# Rapide555.net
KiCad netlist of a schematic drawn in EAGLE
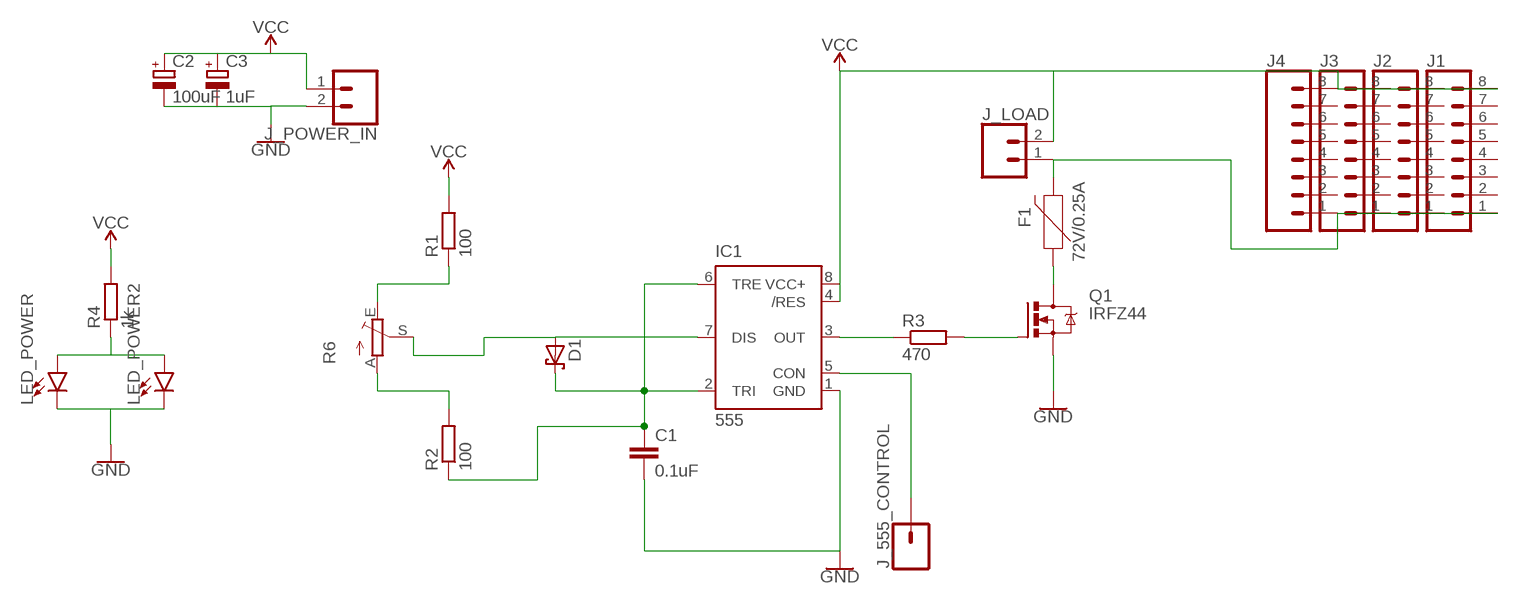
[diagram p0: schematic, sheet 1]

(export (version "E")
  (design (tool "Eeschema 10.0.6"))
  (components
    (comp (ref "C1")
      (value "0.1uF")
      (footprint "eagle-import:C025-025X050")
      (libsource (lib "eagle-import") (part "C-EU025-025X050"))
    )
    (comp (ref "C2")
      (value "100uF")
      (footprint "eagle-import:E5-5")
      (libsource (lib "eagle-import") (part "CPOL-EUE5-5"))
    )
    (comp (ref "C3")
      (value "1uF")
      (footprint "eagle-import:E2,5-6E")
      (libsource (lib "eagle-import") (part "CPOL-EUE2,5-6E"))
    )
    (comp (ref "D1")
      (value "SCHOTTKY-DIODEDO35-7")
      (footprint "eagle-import:DO35-7")
      (libsource (lib "eagle-import") (part "SCHOTTKY-DIODEDO35-7"))
    )
    (comp (ref "F1")
      (value "72V/0.25A")
      (footprint "eagle-import:PTH")
      (libsource (lib "eagle-import") (part "PPTC_PTH"))
    )
    (comp (ref "IC1")
      (value "555")
      (footprint "eagle-import:DIP08")
      (libsource (lib "eagle-import") (part "555P"))
    )
    (comp (ref "J1")
      (value "CONN_08NO_SILK_FEMALE_PTH")
      (footprint "eagle-import:1X08_NO_SILK")
      (libsource (lib "eagle-import") (part "CONN_08NO_SILK_FEMALE_PTH"))
    )
    (comp (ref "J2")
      (value "CONN_08NO_SILK_FEMALE_PTH")
      (footprint "eagle-import:1X08_NO_SILK")
      (libsource (lib "eagle-import") (part "CONN_08NO_SILK_FEMALE_PTH"))
    )
    (comp (ref "J3")
      (value "CONN_08NO_SILK_FEMALE_PTH")
      (footprint "eagle-import:1X08_NO_SILK")
      (libsource (lib "eagle-import") (part "CONN_08NO_SILK_FEMALE_PTH"))
    )
    (comp (ref "J4")
      (value "CONN_08NO_SILK_FEMALE_PTH")
      (footprint "eagle-import:1X08_NO_SILK")
      (libsource (lib "eagle-import") (part "CONN_08NO_SILK_FEMALE_PTH"))
    )
    (comp (ref "J_555_CONTROL")
      (value "CONN_01")
      (footprint "eagle-import:1X01")
      (libsource (lib "eagle-import") (part "CONN_01"))
    )
    (comp (ref "J_LOAD")
      (value "CONN_023.5MM")
      (footprint "eagle-import:SCREWTERMINAL-3.5MM-2")
      (libsource (lib "eagle-import") (part "CONN_023.5MM"))
    )
    (comp (ref "J_POWER_IN")
      (value "CONN_023.5MM")
      (footprint "eagle-import:SCREWTERMINAL-3.5MM-2")
      (libsource (lib "eagle-import") (part "CONN_023.5MM"))
    )
    (comp (ref "LED_POWER")
      (value "LED3MM")
      (footprint "eagle-import:LED_3MM")
      (libsource (lib "eagle-import") (part "LED3MM"))
    )
    (comp (ref "LED_POWER2")
      (value "LED-FKIT-1206")
      (footprint "eagle-import:FKIT-LED-1206")
      (libsource (lib "eagle-import") (part "LED-FKIT-1206"))
    )
    (comp (ref "Q1")
      (value "IRFZ44")
      (footprint "eagle-import:TO-247AD-V")
      (libsource (lib "eagle-import") (part "IXF?6NH90"))
    )
    (comp (ref "R1")
      (value "100")
      (footprint "eagle-import:0204_5")
      (libsource (lib "eagle-import") (part "R-EU_0204/5"))
    )
    (comp (ref "R2")
      (value "100")
      (footprint "eagle-import:0204V")
      (libsource (lib "eagle-import") (part "R-EU_0204/2V"))
    )
    (comp (ref "R3")
      (value "470")
      (footprint "eagle-import:0204_5")
      (libsource (lib "eagle-import") (part "R-EU_0204/5"))
    )
    (comp (ref "R4")
      (value "1k")
      (footprint "eagle-import:0204V")
      (libsource (lib "eagle-import") (part "R-EU_0204/2V"))
    )
    (comp (ref "R6")
      (value "TRIM_EU-B25P")
      (footprint "eagle-import:B25P")
      (libsource (lib "eagle-import") (part "TRIM_EU-B25P"))
    )
  )
  (nets
    (net (code "1") (name "GND") (class "Default")
      (node (ref "C1") (pin "2") (pinfunction "2_2") (pintype "passive"))
      (node (ref "C2") (pin "-") (pinfunction "-_-") (pintype "passive"))
      (node (ref "C3") (pin "-") (pinfunction "-_-") (pintype "passive"))
      (node (ref "IC1") (pin "1") (pinfunction "GND_1") (pintype "power_in"))
      (node (ref "J_POWER_IN") (pin "2") (pinfunction "2_2") (pintype "passive"))
      (node (ref "LED_POWER") (pin "K") (pinfunction "C_K") (pintype "passive"))
      (node (ref "LED_POWER2") (pin "C") (pinfunction "C_C") (pintype "passive"))
      (node (ref "Q1") (pin "S") (pinfunction "S_S") (pintype "passive"))
    )
    (net (code "2") (name "Net-(F1-1)") (class "Default")
      (node (ref "F1") (pin "P$1") (pinfunction "1_P$1") (pintype "bidirectional"))
      (node (ref "Q1") (pin "D") (pinfunction "D_D") (pintype "passive"))
    )
    (net (code "3") (name "Net-(F1-2)") (class "Default")
      (node (ref "F1") (pin "P$2") (pinfunction "2_P$2") (pintype "bidirectional"))
      (node (ref "J1") (pin "1") (pinfunction "1_1") (pintype "passive"))
      (node (ref "J2") (pin "1") (pinfunction "1_1") (pintype "passive"))
      (node (ref "J3") (pin "1") (pinfunction "1_1") (pintype "passive"))
      (node (ref "J4") (pin "1") (pinfunction "1_1") (pintype "passive"))
      (node (ref "J_LOAD") (pin "1") (pinfunction "1_1") (pintype "passive"))
    )
    (net (code "4") (name "Net-(IC1-CON)") (class "Default")
      (node (ref "IC1") (pin "5") (pinfunction "CON_5") (pintype "input"))
      (node (ref "J_555_CONTROL") (pin "1") (pinfunction "1_1") (pintype "passive"))
    )
    (net (code "5") (name "Net-(IC1-DIS)") (class "Default")
      (node (ref "D1") (pin "A") (pinfunction "A_A") (pintype "passive"))
      (node (ref "IC1") (pin "7") (pinfunction "DIS_7") (pintype "input"))
      (node (ref "R6") (pin "S") (pinfunction "S_S") (pintype "passive"))
    )
    (net (code "6") (name "Net-(IC1-OUT)") (class "Default")
      (node (ref "IC1") (pin "3") (pinfunction "OUT_3") (pintype "output"))
      (node (ref "R3") (pin "1") (pinfunction "1_1") (pintype "passive"))
    )
    (net (code "7") (name "Net-(IC1-TRE)") (class "Default")
      (node (ref "C1") (pin "1") (pinfunction "1_1") (pintype "passive"))
      (node (ref "D1") (pin "C") (pinfunction "C_C") (pintype "passive"))
      (node (ref "IC1") (pin "2") (pinfunction "TRI_2") (pintype "input"))
      (node (ref "IC1") (pin "6") (pinfunction "TRE_6") (pintype "input"))
      (node (ref "R2") (pin "1") (pinfunction "1_1") (pintype "passive"))
    )
    (net (code "8") (name "Net-(LED_POWER-PadA)") (class "Default")
      (node (ref "LED_POWER") (pin "A") (pinfunction "A_A") (pintype "passive"))
      (node (ref "LED_POWER2") (pin "A") (pinfunction "A_A") (pintype "passive"))
      (node (ref "R4") (pin "1") (pinfunction "1_1") (pintype "passive"))
    )
    (net (code "9") (name "Net-(Q1-PadG)") (class "Default")
      (node (ref "Q1") (pin "G") (pinfunction "G_G") (pintype "passive"))
      (node (ref "R3") (pin "2") (pinfunction "2_2") (pintype "passive"))
    )
    (net (code "10") (name "Net-(R1-Pad1)") (class "Default")
      (node (ref "R1") (pin "1") (pinfunction "1_1") (pintype "passive"))
      (node (ref "R6") (pin "E") (pinfunction "E_E") (pintype "passive"))
    )
    (net (code "11") (name "Net-(R2-Pad2)") (class "Default")
      (node (ref "R2") (pin "2") (pinfunction "2_2") (pintype "passive"))
      (node (ref "R6") (pin "A") (pinfunction "A_A") (pintype "passive"))
    )
    (net (code "12") (name "VCC") (class "Default")
      (node (ref "C2") (pin "+") (pinfunction "+_+") (pintype "passive"))
      (node (ref "C3") (pin "+") (pinfunction "+_+") (pintype "passive"))
      (node (ref "IC1") (pin "4") (pinfunction "/RES_4") (pintype "input"))
      (node (ref "IC1") (pin "8") (pinfunction "VCC+_8") (pintype "power_in"))
      (node (ref "J1") (pin "8") (pinfunction "8_8") (pintype "passive"))
      (node (ref "J2") (pin "8") (pinfunction "8_8") (pintype "passive"))
      (node (ref "J3") (pin "8") (pinfunction "8_8") (pintype "passive"))
      (node (ref "J4") (pin "8") (pinfunction "8_8") (pintype "passive"))
      (node (ref "J_LOAD") (pin "2") (pinfunction "2_2") (pintype "passive"))
      (node (ref "J_POWER_IN") (pin "1") (pinfunction "1_1") (pintype "passive"))
      (node (ref "R1") (pin "2") (pinfunction "2_2") (pintype "passive"))
      (node (ref "R4") (pin "2") (pinfunction "2_2") (pintype "passive"))
    )
    (net (code "13") (name "unconnected-(J1-Pad2)") (class "Default")
      (node (ref "J1") (pin "2") (pinfunction "2_2") (pintype "passive"))
    )
    (net (code "14") (name "unconnected-(J1-Pad3)") (class "Default")
      (node (ref "J1") (pin "3") (pinfunction "3_3") (pintype "passive"))
    )
    (net (code "15") (name "unconnected-(J1-Pad4)") (class "Default")
      (node (ref "J1") (pin "4") (pinfunction "4_4") (pintype "passive"))
    )
    (net (code "16") (name "unconnected-(J1-Pad5)") (class "Default")
      (node (ref "J1") (pin "5") (pinfunction "5_5") (pintype "passive"))
    )
    (net (code "17") (name "unconnected-(J1-Pad6)") (class "Default")
      (node (ref "J1") (pin "6") (pinfunction "6_6") (pintype "passive"))
    )
    (net (code "18") (name "unconnected-(J1-Pad7)") (class "Default")
      (node (ref "J1") (pin "7") (pinfunction "7_7") (pintype "passive"))
    )
    (net (code "19") (name "unconnected-(J2-Pad2)") (class "Default")
      (node (ref "J2") (pin "2") (pinfunction "2_2") (pintype "passive"))
    )
    (net (code "20") (name "unconnected-(J2-Pad3)") (class "Default")
      (node (ref "J2") (pin "3") (pinfunction "3_3") (pintype "passive"))
    )
    (net (code "21") (name "unconnected-(J2-Pad4)") (class "Default")
      (node (ref "J2") (pin "4") (pinfunction "4_4") (pintype "passive"))
    )
    (net (code "22") (name "unconnected-(J2-Pad5)") (class "Default")
      (node (ref "J2") (pin "5") (pinfunction "5_5") (pintype "passive"))
    )
    (net (code "23") (name "unconnected-(J2-Pad6)") (class "Default")
      (node (ref "J2") (pin "6") (pinfunction "6_6") (pintype "passive"))
    )
    (net (code "24") (name "unconnected-(J2-Pad7)") (class "Default")
      (node (ref "J2") (pin "7") (pinfunction "7_7") (pintype "passive"))
    )
    (net (code "25") (name "unconnected-(J3-Pad2)") (class "Default")
      (node (ref "J3") (pin "2") (pinfunction "2_2") (pintype "passive"))
    )
    (net (code "26") (name "unconnected-(J3-Pad3)") (class "Default")
      (node (ref "J3") (pin "3") (pinfunction "3_3") (pintype "passive"))
    )
    (net (code "27") (name "unconnected-(J3-Pad4)") (class "Default")
      (node (ref "J3") (pin "4") (pinfunction "4_4") (pintype "passive"))
    )
    (net (code "28") (name "unconnected-(J3-Pad5)") (class "Default")
      (node (ref "J3") (pin "5") (pinfunction "5_5") (pintype "passive"))
    )
    (net (code "29") (name "unconnected-(J3-Pad6)") (class "Default")
      (node (ref "J3") (pin "6") (pinfunction "6_6") (pintype "passive"))
    )
    (net (code "30") (name "unconnected-(J3-Pad7)") (class "Default")
      (node (ref "J3") (pin "7") (pinfunction "7_7") (pintype "passive"))
    )
    (net (code "31") (name "unconnected-(J4-Pad2)") (class "Default")
      (node (ref "J4") (pin "2") (pinfunction "2_2") (pintype "passive"))
    )
    (net (code "32") (name "unconnected-(J4-Pad3)") (class "Default")
      (node (ref "J4") (pin "3") (pinfunction "3_3") (pintype "passive"))
    )
    (net (code "33") (name "unconnected-(J4-Pad4)") (class "Default")
      (node (ref "J4") (pin "4") (pinfunction "4_4") (pintype "passive"))
    )
    (net (code "34") (name "unconnected-(J4-Pad5)") (class "Default")
      (node (ref "J4") (pin "5") (pinfunction "5_5") (pintype "passive"))
    )
    (net (code "35") (name "unconnected-(J4-Pad6)") (class "Default")
      (node (ref "J4") (pin "6") (pinfunction "6_6") (pintype "passive"))
    )
    (net (code "36") (name "unconnected-(J4-Pad7)") (class "Default")
      (node (ref "J4") (pin "7") (pinfunction "7_7") (pintype "passive"))
    )
  )
)
